# ReflowController.net
KiCad netlist of a schematic drawn in EAGLE
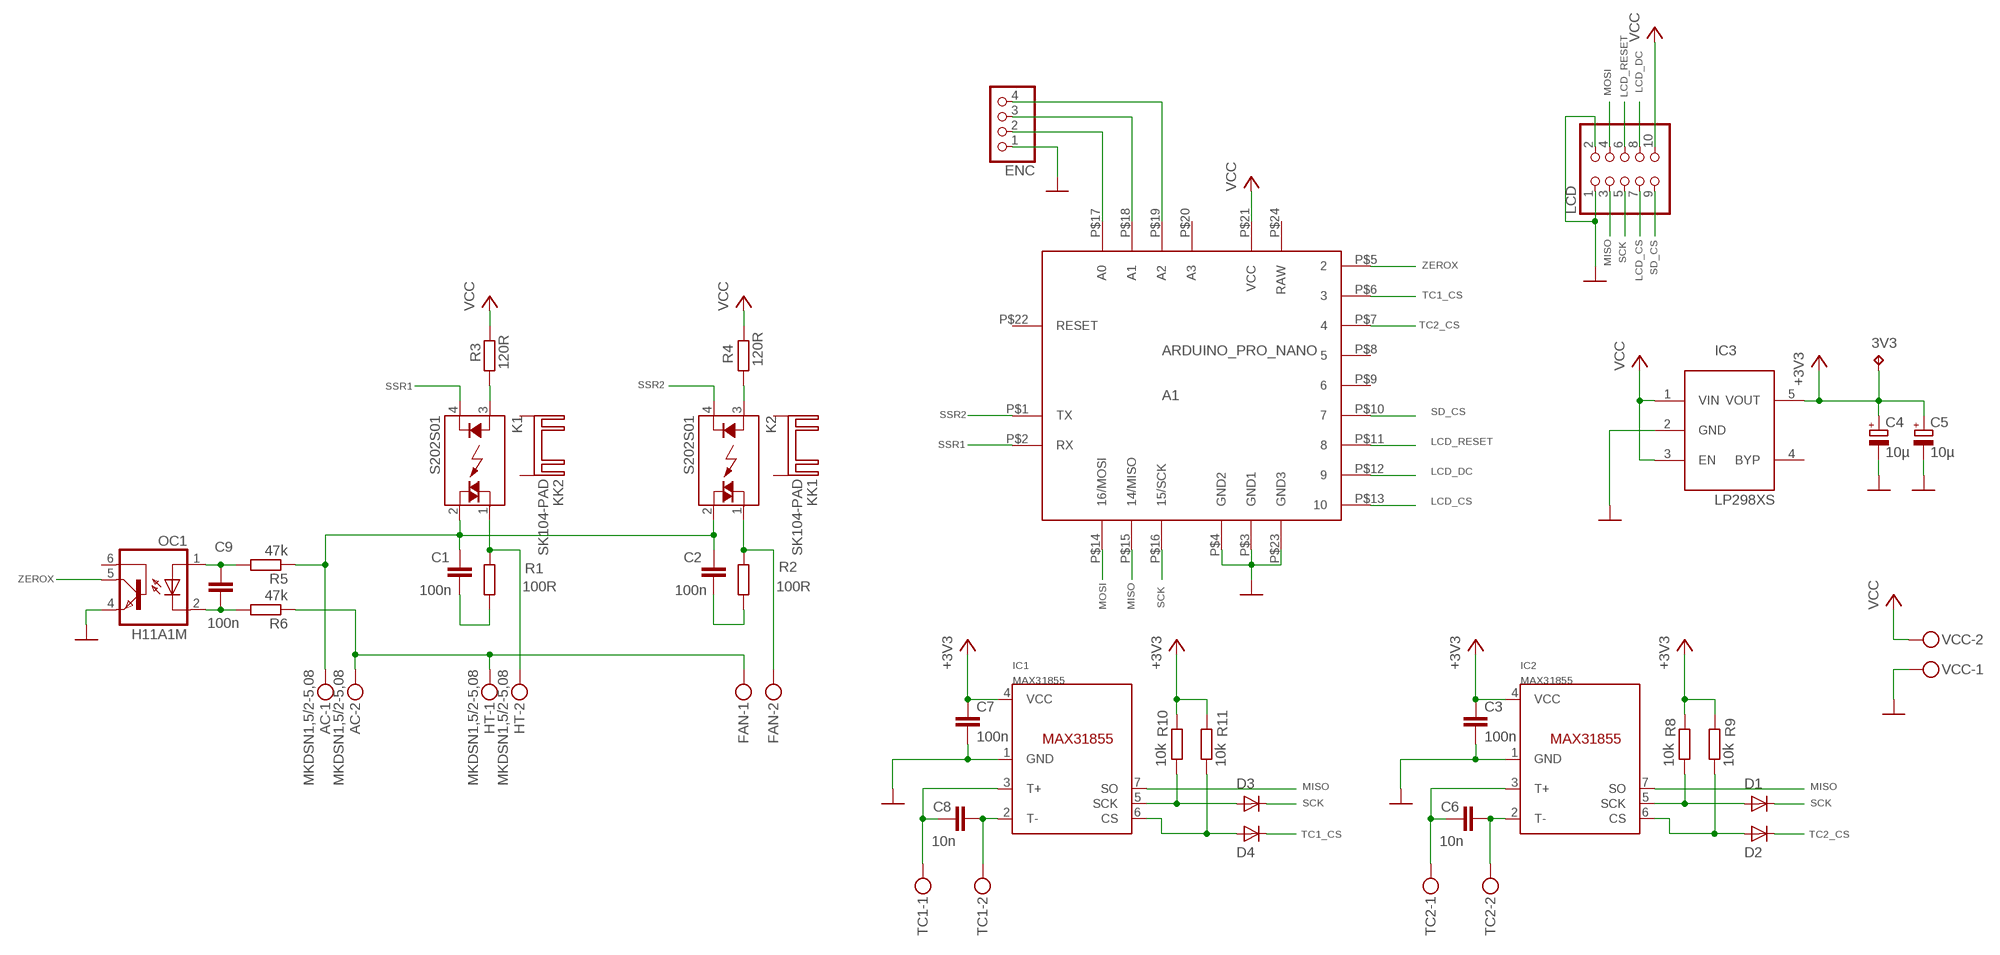
[diagram p0: schematic, sheet 1]

(export (version "E")
  (design (tool "Eeschema 10.0.6"))
  (components
    (comp (ref "3V3")
      (value "TPTP08R")
      (footprint "eagle-import:TP08R")
      (libsource (lib "eagle-import") (part "TPTP08R"))
    )
    (comp (ref "A1")
      (value "ARDUINO_PRO_NANO")
      (footprint "eagle-import:ARDUINO_PRO_NANO")
      (libsource (lib "eagle-import") (part "ARDUINO_PRO_NANO"))
    )
    (comp (ref "AC")
      (value "MKDSN1,5/2-5,08")
      (footprint "eagle-import:MKDSN1,5_2-5,08")
      (fields (field (name "MPN") "MKDSN 1,5/2-5.08"))
      (libsource (lib "eagle-import") (part "MKDSN1,5/2-5,08"))
    )
    (comp (ref "C1")
      (value "100n")
      (footprint "eagle-import:XC10B5")
      (libsource (lib "eagle-import") (part "CXXC10B5"))
    )
    (comp (ref "C2")
      (value "100n")
      (footprint "eagle-import:XC10B5")
      (libsource (lib "eagle-import") (part "CXXC10B5"))
    )
    (comp (ref "C3")
      (value "100n")
      (footprint "eagle-import:C0805")
      (libsource (lib "eagle-import") (part "C-EUC0805"))
    )
    (comp (ref "C4")
      (value "10µ")
      (footprint "eagle-import:C_6032-28R")
      (libsource (lib "eagle-import") (part "CPOL-EUC/6032-28R"))
    )
    (comp (ref "C5")
      (value "10µ")
      (footprint "eagle-import:C_6032-28R")
      (libsource (lib "eagle-import") (part "CPOL-EUC/6032-28R"))
    )
    (comp (ref "C6")
      (value "10n")
      (footprint "eagle-import:C0603")
      (libsource (lib "eagle-import") (part "C-EUC0603"))
    )
    (comp (ref "C7")
      (value "100n")
      (footprint "eagle-import:C0805")
      (libsource (lib "eagle-import") (part "C-EUC0805"))
    )
    (comp (ref "C8")
      (value "10n")
      (footprint "eagle-import:C0603")
      (libsource (lib "eagle-import") (part "C-EUC0603"))
    )
    (comp (ref "C9")
      (value "100n")
      (footprint "eagle-import:C025-025X050")
      (libsource (lib "eagle-import") (part "C-EU025-025X050"))
    )
    (comp (ref "D1")
      (value "DIODESOD-123")
      (footprint "eagle-import:SOD-123")
      (libsource (lib "eagle-import") (part "DIODESOD-123"))
    )
    (comp (ref "D2")
      (value "DIODESOD-123")
      (footprint "eagle-import:SOD-123")
      (libsource (lib "eagle-import") (part "DIODESOD-123"))
    )
    (comp (ref "D3")
      (value "DIODESOD-123")
      (footprint "eagle-import:SOD-123")
      (libsource (lib "eagle-import") (part "DIODESOD-123"))
    )
    (comp (ref "D4")
      (value "DIODESOD-123")
      (footprint "eagle-import:SOD-123")
      (libsource (lib "eagle-import") (part "DIODESOD-123"))
    )
    (comp (ref "ENC")
      (value "PINHD-1X4")
      (footprint "eagle-import:1X04")
      (libsource (lib "eagle-import") (part "PINHD-1X4"))
    )
    (comp (ref "FAN")
      (value "MKDSN1,5/2-5,08")
      (footprint "eagle-import:MKDSN1,5_2-5,08")
      (fields (field (name "MPN") "MKDSN 1,5/2-5.08"))
      (libsource (lib "eagle-import") (part "MKDSN1,5/2-5,08"))
    )
    (comp (ref "HT")
      (value "MKDSN1,5/2-5,08")
      (footprint "eagle-import:MKDSN1,5_2-5,08")
      (fields (field (name "MPN") "MKDSN 1,5/2-5.08"))
      (libsource (lib "eagle-import") (part "MKDSN1,5/2-5,08"))
    )
    (comp (ref "IC1")
      (value "MAX31855")
      (footprint "eagle-import:SOIC8")
      (libsource (lib "eagle-import") (part "MAX31855"))
    )
    (comp (ref "IC2")
      (value "MAX31855")
      (footprint "eagle-import:SOIC8")
      (libsource (lib "eagle-import") (part "MAX31855"))
    )
    (comp (ref "IC3")
      (value "LP298XS")
      (footprint "eagle-import:SOT23-5L")
      (libsource (lib "eagle-import") (part "LP298XS"))
    )
    (comp (ref "K1")
      (value "S202S01")
      (footprint "eagle-import:S102S01")
      (fields (field (name "MPN") "S202S01F"))
      (libsource (lib "eagle-import") (part "S?202S01"))
    )
    (comp (ref "K2")
      (value "S202S01")
      (footprint "eagle-import:S102S01")
      (fields (field (name "MPN") "S202S01F"))
      (libsource (lib "eagle-import") (part "S?202S01"))
    )
    (comp (ref "KK1")
      (value "SK104-PAD")
      (footprint "eagle-import:SK104-PAD")
      (libsource (lib "eagle-import") (part "SK104-PAD"))
    )
    (comp (ref "KK2")
      (value "SK104-PAD")
      (footprint "eagle-import:SK104-PAD")
      (libsource (lib "eagle-import") (part "SK104-PAD"))
    )
    (comp (ref "LCD")
      (value "PINHD-2X5")
      (footprint "eagle-import:2X05")
      (libsource (lib "eagle-import") (part "PINHD-2X5"))
    )
    (comp (ref "OC1")
      (value "H11A1M")
      (footprint "eagle-import:DIL06")
      (fields (field (name "MPN") "H11A1-M"))
      (libsource (lib "eagle-import") (part "H11A?M1"))
    )
    (comp (ref "R1")
      (value "100R")
      (footprint "eagle-import:0207_5V")
      (libsource (lib "eagle-import") (part "R-EU_0207/5V"))
    )
    (comp (ref "R2")
      (value "100R")
      (footprint "eagle-import:0207_5V")
      (libsource (lib "eagle-import") (part "R-EU_0207/5V"))
    )
    (comp (ref "R3")
      (value "120R")
      (footprint "eagle-import:R0603")
      (libsource (lib "eagle-import") (part "R-EU_R0603"))
    )
    (comp (ref "R4")
      (value "120R")
      (footprint "eagle-import:R0603")
      (libsource (lib "eagle-import") (part "R-EU_R0603"))
    )
    (comp (ref "R5")
      (value "47k")
      (footprint "eagle-import:0207_5V")
      (libsource (lib "eagle-import") (part "R-EU_0207/5V"))
    )
    (comp (ref "R6")
      (value "47k")
      (footprint "eagle-import:0207_5V")
      (libsource (lib "eagle-import") (part "R-EU_0207/5V"))
    )
    (comp (ref "R8")
      (value "10k")
      (footprint "eagle-import:R0603")
      (libsource (lib "eagle-import") (part "R-EU_R0603"))
    )
    (comp (ref "R9")
      (value "10k")
      (footprint "eagle-import:R0603")
      (libsource (lib "eagle-import") (part "R-EU_R0603"))
    )
    (comp (ref "R10")
      (value "10k")
      (footprint "eagle-import:R0603")
      (libsource (lib "eagle-import") (part "R-EU_R0603"))
    )
    (comp (ref "R11")
      (value "10k")
      (footprint "eagle-import:R0603")
      (libsource (lib "eagle-import") (part "R-EU_R0603"))
    )
    (comp (ref "TC1")
      (value "MKDSN1,5/2-5,08")
      (footprint "eagle-import:MKDSN1,5_2-5,08")
      (fields (field (name "MPN") "MKDSN 1,5/2-5.08"))
      (libsource (lib "eagle-import") (part "MKDSN1,5/2-5,08"))
    )
    (comp (ref "TC2")
      (value "MKDSN1,5/2-5,08")
      (footprint "eagle-import:MKDSN1,5_2-5,08")
      (fields (field (name "MPN") "MKDSN 1,5/2-5.08"))
      (libsource (lib "eagle-import") (part "MKDSN1,5/2-5,08"))
    )
    (comp (ref "VCC")
      (value "MKDSN1,5/2-5,08")
      (footprint "eagle-import:MKDSN1,5_2-5,08")
      (fields (field (name "MPN") "MKDSN 1,5/2-5.08"))
      (libsource (lib "eagle-import") (part "MKDSN1,5/2-5,08"))
    )
  )
  (nets
    (net (code "1") (name "+3V3") (class "Default")
      (node (ref "3V3") (pin "TP") (pinfunction "TP_TP") (pintype "input"))
      (node (ref "C3") (pin "1") (pinfunction "1_1") (pintype "passive"))
      (node (ref "C4") (pin "+") (pinfunction "+_+") (pintype "passive"))
      (node (ref "C5") (pin "+") (pinfunction "+_+") (pintype "passive"))
      (node (ref "C7") (pin "1") (pinfunction "1_1") (pintype "passive"))
      (node (ref "IC1") (pin "4") (pinfunction "VCC_4") (pintype "power_in"))
      (node (ref "IC2") (pin "4") (pinfunction "VCC_4") (pintype "power_in"))
      (node (ref "IC3") (pin "5") (pinfunction "VOUT_5") (pintype "bidirectional"))
      (node (ref "R10") (pin "2") (pinfunction "2_2") (pintype "passive"))
      (node (ref "R11") (pin "2") (pinfunction "2_2") (pintype "passive"))
      (node (ref "R8") (pin "2") (pinfunction "2_2") (pintype "passive"))
      (node (ref "R9") (pin "2") (pinfunction "2_2") (pintype "passive"))
    )
    (net (code "2") (name "/LCD_CS") (class "Default")
      (node (ref "A1") (pin "P$13") (pinfunction "10_P$13") (pintype "bidirectional"))
      (node (ref "LCD") (pin "7") (pinfunction "7_7") (pintype "passive"))
    )
    (net (code "3") (name "/LCD_DC") (class "Default")
      (node (ref "A1") (pin "P$12") (pinfunction "9_P$12") (pintype "bidirectional"))
      (node (ref "LCD") (pin "8") (pinfunction "8_8") (pintype "passive"))
    )
    (net (code "4") (name "/LCD_RESET") (class "Default")
      (node (ref "A1") (pin "P$11") (pinfunction "8_P$11") (pintype "bidirectional"))
      (node (ref "LCD") (pin "6") (pinfunction "6_6") (pintype "passive"))
    )
    (net (code "5") (name "/MISO") (class "Default")
      (node (ref "A1") (pin "P$15") (pinfunction "14/MISO_P$15") (pintype "bidirectional"))
      (node (ref "IC1") (pin "7") (pinfunction "SO_7") (pintype "output"))
      (node (ref "IC2") (pin "7") (pinfunction "SO_7") (pintype "output"))
      (node (ref "LCD") (pin "3") (pinfunction "3_3") (pintype "passive"))
    )
    (net (code "6") (name "/MOSI") (class "Default")
      (node (ref "A1") (pin "P$14") (pinfunction "16/MOSI_P$14") (pintype "bidirectional"))
      (node (ref "LCD") (pin "4") (pinfunction "4_4") (pintype "passive"))
    )
    (net (code "7") (name "/RAW") (class "Default")
      (node (ref "A1") (pin "P$24") (pinfunction "RAW_P$24") (pintype "power_in"))
    )
    (net (code "8") (name "/SCK") (class "Default")
      (node (ref "A1") (pin "P$16") (pinfunction "15/SCK_P$16") (pintype "bidirectional"))
      (node (ref "D1") (pin "C") (pinfunction "C_C") (pintype "passive"))
      (node (ref "D3") (pin "C") (pinfunction "C_C") (pintype "passive"))
      (node (ref "LCD") (pin "5") (pinfunction "5_5") (pintype "passive"))
    )
    (net (code "9") (name "/SD_CS") (class "Default")
      (node (ref "A1") (pin "P$10") (pinfunction "7_P$10") (pintype "bidirectional"))
      (node (ref "LCD") (pin "9") (pinfunction "9_9") (pintype "passive"))
    )
    (net (code "10") (name "/SSR1") (class "Default")
      (node (ref "A1") (pin "P$2") (pinfunction "RX_P$2") (pintype "bidirectional"))
      (node (ref "K1") (pin "4") (pinfunction "K_4") (pintype "passive"))
    )
    (net (code "11") (name "/SSR2") (class "Default")
      (node (ref "A1") (pin "P$1") (pinfunction "TX_P$1") (pintype "bidirectional"))
      (node (ref "K2") (pin "4") (pinfunction "K_4") (pintype "passive"))
    )
    (net (code "12") (name "/TC1_CS") (class "Default")
      (node (ref "A1") (pin "P$6") (pinfunction "3_P$6") (pintype "bidirectional"))
      (node (ref "D4") (pin "C") (pinfunction "C_C") (pintype "passive"))
    )
    (net (code "13") (name "/TC2_CS") (class "Default")
      (node (ref "A1") (pin "P$7") (pinfunction "4_P$7") (pintype "bidirectional"))
      (node (ref "D2") (pin "C") (pinfunction "C_C") (pintype "passive"))
    )
    (net (code "14") (name "/ZEROX") (class "Default")
      (node (ref "A1") (pin "P$5") (pinfunction "2_P$5") (pintype "bidirectional"))
      (node (ref "OC1") (pin "5") (pinfunction "COL_5") (pintype "passive"))
    )
    (net (code "15") (name "GND") (class "Default")
      (node (ref "A1") (pin "P$23") (pinfunction "GND3_P$23") (pintype "power_in"))
      (node (ref "A1") (pin "P$3") (pinfunction "GND1_P$3") (pintype "power_in"))
      (node (ref "A1") (pin "P$4") (pinfunction "GND2_P$4") (pintype "power_in"))
      (node (ref "C3") (pin "2") (pinfunction "2_2") (pintype "passive"))
      (node (ref "C4") (pin "-") (pinfunction "-_-") (pintype "passive"))
      (node (ref "C5") (pin "-") (pinfunction "-_-") (pintype "passive"))
      (node (ref "C7") (pin "2") (pinfunction "2_2") (pintype "passive"))
      (node (ref "ENC") (pin "1") (pinfunction "1_1") (pintype "passive"))
      (node (ref "IC1") (pin "1") (pinfunction "GND_1") (pintype "power_in"))
      (node (ref "IC2") (pin "1") (pinfunction "GND_1") (pintype "power_in"))
      (node (ref "IC3") (pin "2") (pinfunction "GND_2") (pintype "bidirectional"))
      (node (ref "LCD") (pin "1") (pinfunction "1_1") (pintype "passive"))
      (node (ref "LCD") (pin "2") (pinfunction "2_2") (pintype "passive"))
      (node (ref "OC1") (pin "4") (pinfunction "EMI_4") (pintype "passive"))
      (node (ref "VCC") (pin "1") (pinfunction "KL_1") (pintype "passive"))
    )
    (net (code "16") (name "Net-(A1-A0)") (class "Default")
      (node (ref "A1") (pin "P$17") (pinfunction "A0_P$17") (pintype "bidirectional"))
      (node (ref "ENC") (pin "2") (pinfunction "2_2") (pintype "passive"))
    )
    (net (code "17") (name "Net-(A1-A1)") (class "Default")
      (node (ref "A1") (pin "P$18") (pinfunction "A1_P$18") (pintype "bidirectional"))
      (node (ref "ENC") (pin "3") (pinfunction "3_3") (pintype "passive"))
    )
    (net (code "18") (name "Net-(A1-A2)") (class "Default")
      (node (ref "A1") (pin "P$19") (pinfunction "A2_P$19") (pintype "bidirectional"))
      (node (ref "ENC") (pin "4") (pinfunction "4_4") (pintype "passive"))
    )
    (net (code "19") (name "Net-(ACA-KL)") (class "Default")
      (node (ref "AC") (pin "1") (pinfunction "KL_1") (pintype "passive"))
      (node (ref "C1") (pin "1") (pinfunction "1_1") (pintype "passive"))
      (node (ref "C2") (pin "1") (pinfunction "1_1") (pintype "passive"))
      (node (ref "K1") (pin "2") (pinfunction "DS2_2") (pintype "passive"))
      (node (ref "K2") (pin "2") (pinfunction "DS2_2") (pintype "passive"))
      (node (ref "R5") (pin "1") (pinfunction "1_1") (pintype "passive"))
    )
    (net (code "20") (name "Net-(ACB-KL)") (class "Default")
      (node (ref "AC") (pin "2") (pinfunction "KL_2") (pintype "passive"))
      (node (ref "FAN") (pin "1") (pinfunction "KL_1") (pintype "passive"))
      (node (ref "HT") (pin "1") (pinfunction "KL_1") (pintype "passive"))
      (node (ref "R6") (pin "1") (pinfunction "1_1") (pintype "passive"))
    )
    (net (code "21") (name "Net-(C1-Pad2)") (class "Default")
      (node (ref "C1") (pin "2") (pinfunction "2_2") (pintype "passive"))
      (node (ref "R1") (pin "1") (pinfunction "1_1") (pintype "passive"))
    )
    (net (code "22") (name "Net-(C2-Pad2)") (class "Default")
      (node (ref "C2") (pin "2") (pinfunction "2_2") (pintype "passive"))
      (node (ref "R2") (pin "1") (pinfunction "1_1") (pintype "passive"))
    )
    (net (code "23") (name "Net-(FANB-KL)") (class "Default")
      (node (ref "FAN") (pin "2") (pinfunction "KL_2") (pintype "passive"))
      (node (ref "K2") (pin "1") (pinfunction "DS1_1") (pintype "passive"))
      (node (ref "R2") (pin "2") (pinfunction "2_2") (pintype "passive"))
    )
    (net (code "24") (name "Net-(HTB-KL)") (class "Default")
      (node (ref "HT") (pin "2") (pinfunction "KL_2") (pintype "passive"))
      (node (ref "K1") (pin "1") (pinfunction "DS1_1") (pintype "passive"))
      (node (ref "R1") (pin "2") (pinfunction "2_2") (pintype "passive"))
    )
    (net (code "25") (name "Net-(IC1-CS)") (class "Default")
      (node (ref "D4") (pin "A") (pinfunction "A_A") (pintype "passive"))
      (node (ref "IC1") (pin "6") (pinfunction "CS_6") (pintype "input"))
      (node (ref "R11") (pin "1") (pinfunction "1_1") (pintype "passive"))
    )
    (net (code "26") (name "Net-(IC1-SCK)") (class "Default")
      (node (ref "D3") (pin "A") (pinfunction "A_A") (pintype "passive"))
      (node (ref "IC1") (pin "5") (pinfunction "SCK_5") (pintype "input"))
      (node (ref "R10") (pin "1") (pinfunction "1_1") (pintype "passive"))
    )
    (net (code "27") (name "Net-(IC1-T+)") (class "Default")
      (node (ref "C8") (pin "1") (pinfunction "1_1") (pintype "passive"))
      (node (ref "IC1") (pin "3") (pinfunction "T+_3") (pintype "input"))
      (node (ref "TC1") (pin "1") (pinfunction "KL_1") (pintype "passive"))
    )
    (net (code "28") (name "Net-(IC1-T-)") (class "Default")
      (node (ref "C8") (pin "2") (pinfunction "2_2") (pintype "passive"))
      (node (ref "IC1") (pin "2") (pinfunction "T-_2") (pintype "input"))
      (node (ref "TC1") (pin "2") (pinfunction "KL_2") (pintype "passive"))
    )
    (net (code "29") (name "Net-(IC2-CS)") (class "Default")
      (node (ref "D2") (pin "A") (pinfunction "A_A") (pintype "passive"))
      (node (ref "IC2") (pin "6") (pinfunction "CS_6") (pintype "input"))
      (node (ref "R9") (pin "1") (pinfunction "1_1") (pintype "passive"))
    )
    (net (code "30") (name "Net-(IC2-SCK)") (class "Default")
      (node (ref "D1") (pin "A") (pinfunction "A_A") (pintype "passive"))
      (node (ref "IC2") (pin "5") (pinfunction "SCK_5") (pintype "input"))
      (node (ref "R8") (pin "1") (pinfunction "1_1") (pintype "passive"))
    )
    (net (code "31") (name "Net-(IC2-T+)") (class "Default")
      (node (ref "C6") (pin "1") (pinfunction "1_1") (pintype "passive"))
      (node (ref "IC2") (pin "3") (pinfunction "T+_3") (pintype "input"))
      (node (ref "TC2") (pin "1") (pinfunction "KL_1") (pintype "passive"))
    )
    (net (code "32") (name "Net-(IC2-T-)") (class "Default")
      (node (ref "C6") (pin "2") (pinfunction "2_2") (pintype "passive"))
      (node (ref "IC2") (pin "2") (pinfunction "T-_2") (pintype "input"))
      (node (ref "TC2") (pin "2") (pinfunction "KL_2") (pintype "passive"))
    )
    (net (code "33") (name "Net-(K1-A)") (class "Default")
      (node (ref "K1") (pin "3") (pinfunction "A_3") (pintype "passive"))
      (node (ref "R3") (pin "2") (pinfunction "2_2") (pintype "passive"))
    )
    (net (code "34") (name "Net-(K2-A)") (class "Default")
      (node (ref "K2") (pin "3") (pinfunction "A_3") (pintype "passive"))
      (node (ref "R4") (pin "2") (pinfunction "2_2") (pintype "passive"))
    )
    (net (code "35") (name "Net-(OC1-A)") (class "Default")
      (node (ref "C9") (pin "1") (pinfunction "1_1") (pintype "passive"))
      (node (ref "OC1") (pin "1") (pinfunction "A_1") (pintype "passive"))
      (node (ref "R5") (pin "2") (pinfunction "2_2") (pintype "passive"))
    )
    (net (code "36") (name "Net-(OC1-C)") (class "Default")
      (node (ref "C9") (pin "2") (pinfunction "2_2") (pintype "passive"))
      (node (ref "OC1") (pin "2") (pinfunction "C_2") (pintype "passive"))
      (node (ref "R6") (pin "2") (pinfunction "2_2") (pintype "passive"))
    )
    (net (code "37") (name "VCC") (class "Default")
      (node (ref "A1") (pin "P$21") (pinfunction "VCC_P$21") (pintype "power_in"))
      (node (ref "IC3") (pin "1") (pinfunction "VIN_1") (pintype "bidirectional"))
      (node (ref "IC3") (pin "3") (pinfunction "EN_3") (pintype "bidirectional"))
      (node (ref "LCD") (pin "10") (pinfunction "10_10") (pintype "passive"))
      (node (ref "R3") (pin "1") (pinfunction "1_1") (pintype "passive"))
      (node (ref "R4") (pin "1") (pinfunction "1_1") (pintype "passive"))
      (node (ref "VCC") (pin "2") (pinfunction "KL_2") (pintype "passive"))
    )
    (net (code "38") (name "unconnected-(A1-5-PadP$8)") (class "Default")
      (node (ref "A1") (pin "P$8") (pinfunction "5_P$8") (pintype "bidirectional"))
    )
    (net (code "39") (name "unconnected-(A1-6-PadP$9)") (class "Default")
      (node (ref "A1") (pin "P$9") (pinfunction "6_P$9") (pintype "bidirectional"))
    )
    (net (code "40") (name "unconnected-(A1-A3-PadP$20)") (class "Default")
      (node (ref "A1") (pin "P$20") (pinfunction "A3_P$20") (pintype "bidirectional"))
    )
    (net (code "41") (name "unconnected-(A1-RESET-PadP$22)") (class "Default")
      (node (ref "A1") (pin "P$22") (pinfunction "RESET_P$22") (pintype "bidirectional"))
    )
    (net (code "42") (name "unconnected-(IC3-BYP-Pad4)") (class "Default")
      (node (ref "IC3") (pin "4") (pinfunction "BYP_4") (pintype "bidirectional"))
    )
    (net (code "43") (name "unconnected-(KK1-K-PadK1)") (class "Default")
      (node (ref "KK1") (pin "K1") (pinfunction "K_K1") (pintype "passive"))
    )
    (net (code "44") (name "unconnected-(KK1-K-PadK2)") (class "Default")
      (node (ref "KK1") (pin "K2") (pinfunction "K_K2") (pintype "passive"))
    )
    (net (code "45") (name "unconnected-(KK2-K-PadK1)") (class "Default")
      (node (ref "KK2") (pin "K1") (pinfunction "K_K1") (pintype "passive"))
    )
    (net (code "46") (name "unconnected-(KK2-K-PadK2)") (class "Default")
      (node (ref "KK2") (pin "K2") (pinfunction "K_K2") (pintype "passive"))
    )
    (net (code "47") (name "unconnected-(OC1-BAS-Pad6)") (class "Default")
      (node (ref "OC1") (pin "6") (pinfunction "BAS_6") (pintype "passive"))
    )
  )
)
